# LED_B.net
KiCad netlist of a schematic drawn in Altium Designer
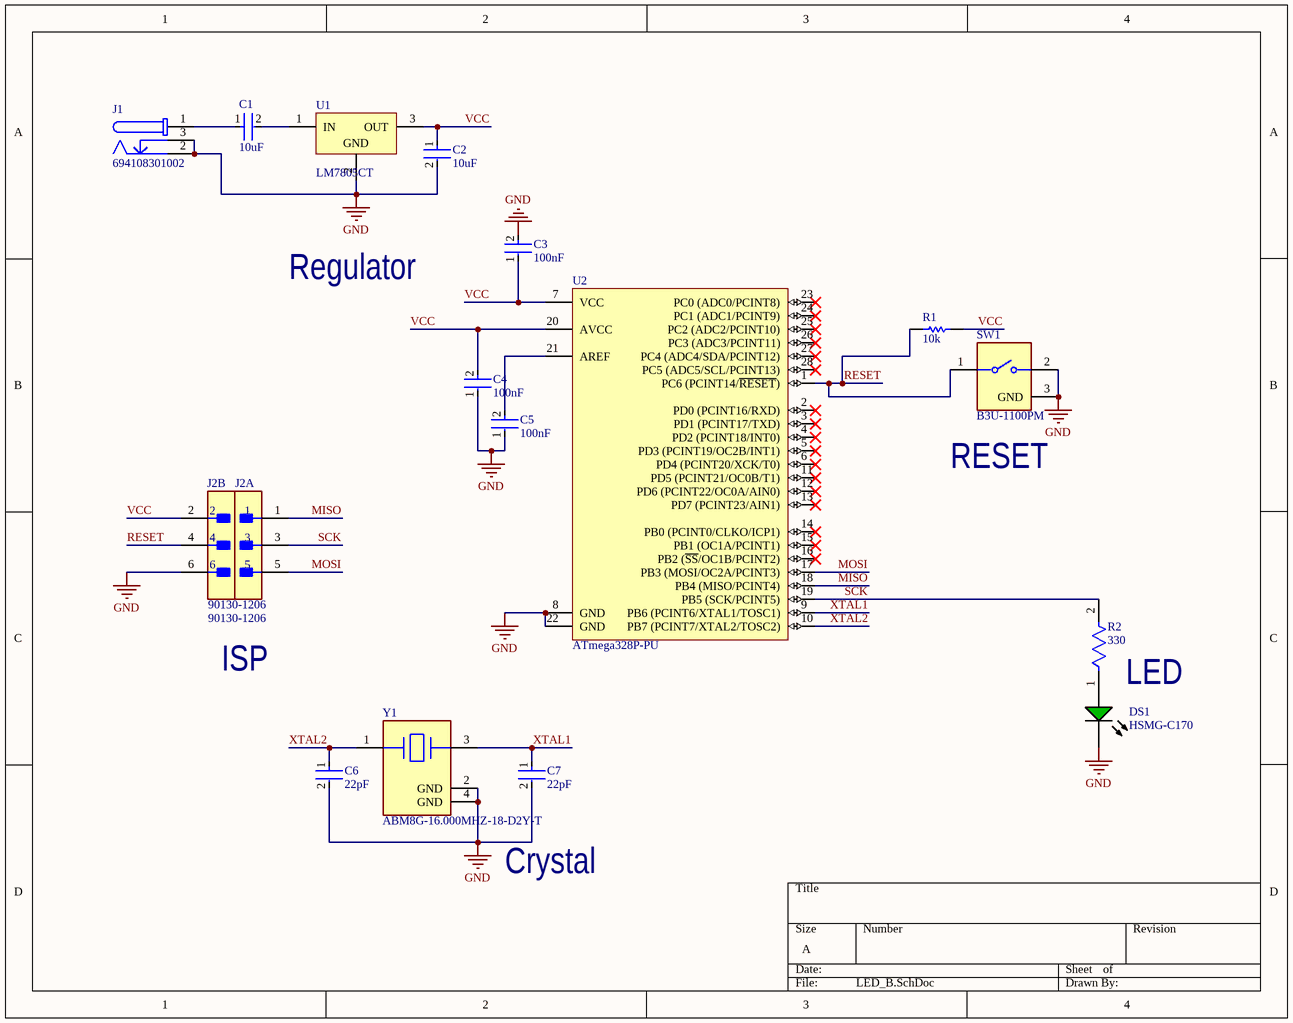
[diagram p0: LED_B.SchDoc]

(export (version "E")
  (design (tool "Eeschema 10.0.6"))
  (components
    (comp (ref "C1")
      (value "10uF")
      (footprint "FP-GRM21B-0_1-IPC_C")
      (description "Chip Multilayer Ceramic Capacitors for General Purpose, 0805, 10uF, X5R, 15%, 10%, 16V")
      (fields (field (name "TOLERANCE") "10%") (field (name "VOLTAGE") "16V"))
      (libsource (lib "Altium Content Vault") (part "b4654b650e69147ec39a6b967a45e02"))
    )
    (comp (ref "C2")
      (value "10uF")
      (footprint "FP-GRM21B-0_1-IPC_C")
      (description "Chip Multilayer Ceramic Capacitors for General Purpose, 0805, 10uF, X5R, 15%, 10%, 16V")
      (fields (field (name "TOLERANCE") "10%") (field (name "VOLTAGE") "16V"))
      (libsource (lib "Altium Content Vault") (part "b4654b650e69147ec39a6b967a45e02"))
    )
    (comp (ref "C3")
      (value "100nF")
      (footprint "FP-GRM15-MFG")
      (description "CAP CER 0.1UF 16V X7R 0402")
      (fields (field (name "MANUFACTURER PART NUMBER") "GRM155R71C104KA88D") (field (name "TOLERANCE") "10%"))
      (libsource (lib "Altium Content Vault") (part "236180d848d6139a670b325ea6854c9"))
    )
    (comp (ref "C4")
      (value "100nF")
      (footprint "FP-GRM15-MFG")
      (description "CAP CER 0.1UF 16V X7R 0402")
      (fields (field (name "MANUFACTURER PART NUMBER") "GRM155R71C104KA88D") (field (name "TOLERANCE") "10%"))
      (libsource (lib "Altium Content Vault") (part "236180d848d6139a670b325ea6854c9"))
    )
    (comp (ref "C5")
      (value "100nF")
      (footprint "FP-GRM15-MFG")
      (description "CAP CER 0.1UF 16V X7R 0402")
      (fields (field (name "MANUFACTURER PART NUMBER") "GRM155R71C104KA88D") (field (name "TOLERANCE") "10%"))
      (libsource (lib "Altium Content Vault") (part "236180d848d6139a670b325ea6854c9"))
    )
    (comp (ref "C6")
      (value "22pF")
      (footprint "FP-C0603C-CF-MFG")
      (description "C0603 22 pF C0G 30ppm/°C 10.00% 16 V")
      (fields (field (name "TOLERANCE") "0.1"))
      (libsource (lib "Altium Content Vault") (part "b4654b650e69147ec39a6b967a45e02"))
    )
    (comp (ref "C7")
      (value "22pF")
      (footprint "FP-C0603C-CF-MFG")
      (description "C0603 22 pF C0G 30ppm/°C 10.00% 16 V")
      (fields (field (name "TOLERANCE") "0.1"))
      (libsource (lib "Altium Content Vault") (part "b4654b650e69147ec39a6b967a45e02"))
    )
    (comp (ref "DS1")
      (value "HSMG-C170")
      (footprint "AVAG-HSMX-C170_V")
      (description "Chip LED, Green, 2.2 V, -40 to 85 degC, 2-Pin SMD, Pb-Free, Tape and Reel")
      (fields (field (name "MANUFACTURER") "Avago"))
      (libsource (lib "Altium Content Vault") (part "LED_GREEN_A1K2-2"))
    )
    (comp (ref "J1")
      (value "694108301002")
      (footprint "694108301002")
      (libsource (lib "Altium Content Vault") (part "DC Power Jack"))
    )
    (comp (ref "J2")
      (value "90130-1206")
      (footprint "FP-90130-1206-MFG")
      (description "CONN HEADER VERT 6POS 2.54MM")
      (libsource (lib "") (part "2654a11fb13586ecb194516b1c997bc_1"))
    )
    (comp (ref "R1")
      (value "10k")
      (footprint "RESC1005X40X25LL05T10")
      (fields (field (name "PART NUMBER") "RC0402FR-0710KL") (field (name "MANUFACTURER") "Yageo / Phycomp"))
      (libsource (lib "Altium Content Vault") (part "RES"))
    )
    (comp (ref "R2")
      (value "330")
      (footprint "FP-CRCW0805-e3-MFG")
      (description "RES Thick Film, 330Ω, 1%, 0.125W, 100ppm/°C, 0805")
      (fields (field (name "TOLERANCE") "1%"))
      (libsource (lib "Altium Content Vault") (part "1029c3af85768c4190bb7ad29bc67b5"))
    )
    (comp (ref "SW1")
      (value "B3U-1100PM")
      (footprint "FP-B3U-1100PM-MFG")
      (description "SWITCH TACTILE SPST-NO 0.05A 12V")
      (libsource (lib "Altium Content Vault") (part "6d7322ea62e06c21cb959ab9578dfa0"))
    )
    (comp (ref "U1")
      (value "LM7805CT")
      (footprint "FAIR-TO-220-3")
      (description "Positive Voltage Regulator, 5 V, 1 A, -40 to 125 degC, 3-Pin TO-220, RoHS, Tube")
      (fields (field (name "MANUFACTURER") "FairchildSemiconductor"))
      (libsource (lib "Altium Content Vault") (part "FAIR-LM7805CT-TO220-3"))
    )
    (comp (ref "U2")
      (value "ATmega328P-PU")
      (footprint "28P3")
      (libsource (lib "Altium Content Vault") (part "MC-8B-ATM48-IL28"))
    )
    (comp (ref "Y1")
      (value "ABM8G-16.000MHZ-18-D2Y-T")
      (footprint "FP-ABM8G-MFG")
      (description "Crystal 16MHz ±20ppm (Tol) ±30ppm (Stability) 18pF FUND 80Ω 4-Pin SMD T/R")
      (fields (field (name "TOLERANCE") "20ppm"))
      (libsource (lib "Altium Content Vault") (part "48e526d86b7f2615d98721063c72f49"))
    )
  )
  (nets
    (net (code "1") (name "/MISO") (class "Default")
      (node (ref "J2") (pin "1") (pinfunction "1_1") (pintype "passive"))
      (node (ref "U2") (pin "18") (pinfunction "PB4_(MISO/PCINT4)_18") (pintype "bidirectional"))
    )
    (net (code "2") (name "/MOSI") (class "Default")
      (node (ref "J2") (pin "5") (pinfunction "5_5") (pintype "passive"))
      (node (ref "U2") (pin "17") (pinfunction "PB3_(MOSI/OC2A/PCINT3)_17") (pintype "bidirectional"))
    )
    (net (code "3") (name "/RESET") (class "Default")
      (node (ref "J2") (pin "4") (pinfunction "4_4") (pintype "passive"))
      (node (ref "R1") (pin "1") (pinfunction "1_1") (pintype "passive"))
      (node (ref "SW1") (pin "1") (pinfunction "1_1") (pintype "passive"))
      (node (ref "U2") (pin "1") (pinfunction "PC6_(PCINT14/~{RESET})_1") (pintype "bidirectional"))
    )
    (net (code "4") (name "/SCK") (class "Default")
      (node (ref "J2") (pin "3") (pinfunction "3_3") (pintype "passive"))
      (node (ref "R2") (pin "2") (pinfunction "2_2") (pintype "passive"))
      (node (ref "U2") (pin "19") (pinfunction "PB5_(SCK/PCINT5)_19") (pintype "bidirectional"))
    )
    (net (code "5") (name "/VCC") (class "Default")
      (node (ref "C2") (pin "1") (pinfunction "1_1") (pintype "passive"))
      (node (ref "C3") (pin "1") (pinfunction "1_1") (pintype "passive"))
      (node (ref "C4") (pin "2") (pinfunction "2_2") (pintype "passive"))
      (node (ref "J2") (pin "2") (pinfunction "2_2") (pintype "passive"))
      (node (ref "R1") (pin "2") (pinfunction "2_2") (pintype "passive"))
      (node (ref "U1") (pin "3") (pinfunction "OUT_3") (pintype "passive"))
      (node (ref "U2") (pin "20") (pinfunction "AVCC_20") (pintype "power_in"))
      (node (ref "U2") (pin "7") (pinfunction "VCC_7") (pintype "power_in"))
    )
    (net (code "6") (name "/XTAL1") (class "Default")
      (node (ref "C7") (pin "1") (pinfunction "1_1") (pintype "passive"))
      (node (ref "U2") (pin "9") (pinfunction "PB6_(PCINT6/XTAL1/TOSC1)_9") (pintype "bidirectional"))
      (node (ref "Y1") (pin "3") (pinfunction "3_3") (pintype "passive"))
    )
    (net (code "7") (name "/XTAL2") (class "Default")
      (node (ref "C6") (pin "1") (pinfunction "1_1") (pintype "passive"))
      (node (ref "U2") (pin "10") (pinfunction "PB7_(PCINT7/XTAL2/TOSC2)_10") (pintype "bidirectional"))
      (node (ref "Y1") (pin "1") (pinfunction "1_1") (pintype "passive"))
    )
    (net (code "8") (name "GND") (class "Default")
      (node (ref "C2") (pin "2") (pinfunction "2_2") (pintype "passive"))
      (node (ref "C3") (pin "2") (pinfunction "2_2") (pintype "passive"))
      (node (ref "C4") (pin "1") (pinfunction "1_1") (pintype "passive"))
      (node (ref "C5") (pin "1") (pinfunction "1_1") (pintype "passive"))
      (node (ref "C6") (pin "2") (pinfunction "2_2") (pintype "passive"))
      (node (ref "C7") (pin "2") (pinfunction "2_2") (pintype "passive"))
      (node (ref "DS1") (pin "2") (pinfunction "K_2") (pintype "passive"))
      (node (ref "J1") (pin "2") (pinfunction "2_2") (pintype "passive"))
      (node (ref "J1") (pin "3") (pinfunction "3_3") (pintype "passive"))
      (node (ref "J2") (pin "6") (pinfunction "6_6") (pintype "passive"))
      (node (ref "SW1") (pin "2") (pinfunction "2_2") (pintype "passive"))
      (node (ref "SW1") (pin "3") (pinfunction "GND_3") (pintype "power_in"))
      (node (ref "U1") (pin "2") (pinfunction "GND_2") (pintype "power_in"))
      (node (ref "U2") (pin "22") (pinfunction "GND_22") (pintype "power_in"))
      (node (ref "U2") (pin "8") (pinfunction "GND_8") (pintype "power_in"))
      (node (ref "Y1") (pin "2") (pinfunction "GND_2") (pintype "power_in"))
      (node (ref "Y1") (pin "4") (pinfunction "GND_4") (pintype "power_in"))
    )
    (net (code "9") (name "Net-(C1-Pad1)") (class "Default")
      (node (ref "C1") (pin "1") (pinfunction "1_1") (pintype "passive"))
      (node (ref "J1") (pin "1") (pinfunction "1_1") (pintype "passive"))
    )
    (net (code "10") (name "Net-(U1-IN)") (class "Default")
      (node (ref "C1") (pin "2") (pinfunction "2_2") (pintype "passive"))
      (node (ref "U1") (pin "1") (pinfunction "IN_1") (pintype "passive"))
    )
    (net (code "11") (name "Net-(U2-AREF)") (class "Default")
      (node (ref "C5") (pin "2") (pinfunction "2_2") (pintype "passive"))
      (node (ref "U2") (pin "21") (pinfunction "AREF_21") (pintype "power_in"))
    )
    (net (code "12") (name "unconnected-(DS1-A-Pad1)") (class "Default")
      (node (ref "DS1") (pin "1") (pinfunction "A_1") (pintype "passive"))
    )
    (net (code "13") (name "unconnected-(R2-Pad1)") (class "Default")
      (node (ref "R2") (pin "1") (pinfunction "1_1") (pintype "passive"))
    )
    (net (code "14") (name "unconnected-(U2-PB0_(PCINT0{slash}CLKO{slash}ICP1)-Pad14)") (class "Default")
      (node (ref "U2") (pin "14") (pinfunction "PB0_(PCINT0/CLKO/ICP1)_14") (pintype "bidirectional+no_connect"))
    )
    (net (code "15") (name "unconnected-(U2-PB1_(OC1A{slash}PCINT1)-Pad15)") (class "Default")
      (node (ref "U2") (pin "15") (pinfunction "PB1_(OC1A/PCINT1)_15") (pintype "bidirectional+no_connect"))
    )
    (net (code "16") (name "unconnected-(U2-PB2_(~{SS}{slash}OC1B{slash}PCINT2)-Pad16)") (class "Default")
      (node (ref "U2") (pin "16") (pinfunction "PB2_(~{SS}/OC1B/PCINT2)_16") (pintype "bidirectional+no_connect"))
    )
    (net (code "17") (name "unconnected-(U2-PC0_(ADC0{slash}PCINT8)-Pad23)") (class "Default")
      (node (ref "U2") (pin "23") (pinfunction "PC0_(ADC0/PCINT8)_23") (pintype "bidirectional+no_connect"))
    )
    (net (code "18") (name "unconnected-(U2-PC1_(ADC1{slash}PCINT9)-Pad24)") (class "Default")
      (node (ref "U2") (pin "24") (pinfunction "PC1_(ADC1/PCINT9)_24") (pintype "bidirectional+no_connect"))
    )
    (net (code "19") (name "unconnected-(U2-PC2_(ADC2{slash}PCINT10)-Pad25)") (class "Default")
      (node (ref "U2") (pin "25") (pinfunction "PC2_(ADC2/PCINT10)_25") (pintype "bidirectional+no_connect"))
    )
    (net (code "20") (name "unconnected-(U2-PC3_(ADC3{slash}PCINT11)-Pad26)") (class "Default")
      (node (ref "U2") (pin "26") (pinfunction "PC3_(ADC3/PCINT11)_26") (pintype "bidirectional+no_connect"))
    )
    (net (code "21") (name "unconnected-(U2-PC4_(ADC4{slash}SDA{slash}PCINT12)-Pad27)") (class "Default")
      (node (ref "U2") (pin "27") (pinfunction "PC4_(ADC4/SDA/PCINT12)_27") (pintype "bidirectional+no_connect"))
    )
    (net (code "22") (name "unconnected-(U2-PC5_(ADC5{slash}SCL{slash}PCINT13)-Pad28)") (class "Default")
      (node (ref "U2") (pin "28") (pinfunction "PC5_(ADC5/SCL/PCINT13)_28") (pintype "bidirectional+no_connect"))
    )
    (net (code "23") (name "unconnected-(U2-PD0_(PCINT16{slash}RXD)-Pad2)") (class "Default")
      (node (ref "U2") (pin "2") (pinfunction "PD0_(PCINT16/RXD)_2") (pintype "bidirectional+no_connect"))
    )
    (net (code "24") (name "unconnected-(U2-PD1_(PCINT17{slash}TXD)-Pad3)") (class "Default")
      (node (ref "U2") (pin "3") (pinfunction "PD1_(PCINT17/TXD)_3") (pintype "bidirectional+no_connect"))
    )
    (net (code "25") (name "unconnected-(U2-PD2_(PCINT18{slash}INT0)-Pad4)") (class "Default")
      (node (ref "U2") (pin "4") (pinfunction "PD2_(PCINT18/INT0)_4") (pintype "bidirectional+no_connect"))
    )
    (net (code "26") (name "unconnected-(U2-PD3_(PCINT19{slash}OC2B{slash}INT1)-Pad5)") (class "Default")
      (node (ref "U2") (pin "5") (pinfunction "PD3_(PCINT19/OC2B/INT1)_5") (pintype "bidirectional+no_connect"))
    )
    (net (code "27") (name "unconnected-(U2-PD4_(PCINT20{slash}XCK{slash}T0)-Pad6)") (class "Default")
      (node (ref "U2") (pin "6") (pinfunction "PD4_(PCINT20/XCK/T0)_6") (pintype "bidirectional+no_connect"))
    )
    (net (code "28") (name "unconnected-(U2-PD5_(PCINT21{slash}OC0B{slash}T1)-Pad11)") (class "Default")
      (node (ref "U2") (pin "11") (pinfunction "PD5_(PCINT21/OC0B/T1)_11") (pintype "bidirectional+no_connect"))
    )
    (net (code "29") (name "unconnected-(U2-PD6_(PCINT22{slash}OC0A{slash}AIN0)-Pad12)") (class "Default")
      (node (ref "U2") (pin "12") (pinfunction "PD6_(PCINT22/OC0A/AIN0)_12") (pintype "bidirectional+no_connect"))
    )
    (net (code "30") (name "unconnected-(U2-PD7_(PCINT23{slash}AIN1)-Pad13)") (class "Default")
      (node (ref "U2") (pin "13") (pinfunction "PD7_(PCINT23/AIN1)_13") (pintype "bidirectional+no_connect"))
    )
  )
)
